# V4.net
KiCad netlist of a schematic drawn in Altium Designer
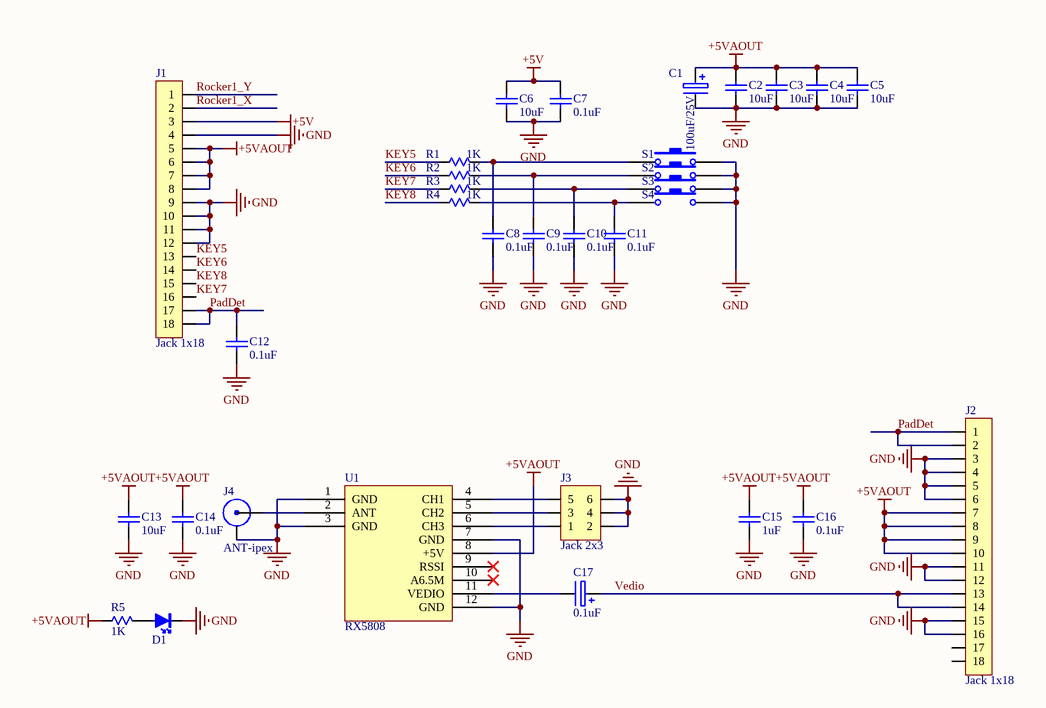
[diagram p0: 海关全向控制器图传转接板V4.SchDoc]

(export (version "E")
  (design (tool "Eeschema 10.0.6"))
  (components
    (comp (ref "C1") (value "100uF/25V") (footprint "C7343") (libsource (lib "RLCYDF") (part "Cap Poll")))
    (comp (ref "C2") (value "10uF") (footprint "C0805") (libsource (lib "SMD") (part "Cap Semi")))
    (comp (ref "C3") (value "10uF") (footprint "C0805") (libsource (lib "SMD") (part "Cap Semi")))
    (comp (ref "C4") (value "10uF") (footprint "C0805") (libsource (lib "SMD") (part "Cap Semi")))
    (comp (ref "C5") (value "10uF") (footprint "C0805") (libsource (lib "SMD") (part "Cap Semi")))
    (comp (ref "C6") (value "10uF") (footprint "C0805") (libsource (lib "SMD") (part "Cap Semi")))
    (comp (ref "C7") (value "0.1uF") (footprint "C0805") (libsource (lib "SMD") (part "Cap Semi")))
    (comp (ref "C8") (value "0.1uF") (footprint "C0805") (libsource (lib "SMD") (part "Cap Semi")))
    (comp (ref "C9") (value "0.1uF") (footprint "C0805") (libsource (lib "SMD") (part "Cap Semi")))
    (comp (ref "C10") (value "0.1uF") (footprint "C0805") (libsource (lib "SMD") (part "Cap Semi")))
    (comp (ref "C11") (value "0.1uF") (footprint "C0805") (libsource (lib "SMD") (part "Cap Semi")))
    (comp (ref "C12") (value "0.1uF") (footprint "C0805") (libsource (lib "SMD") (part "Cap Semi")))
    (comp (ref "C13") (value "10uF") (footprint "C0805") (libsource (lib "SMD") (part "Cap Semi")))
    (comp (ref "C14") (value "0.1uF") (footprint "C0805") (libsource (lib "SMD") (part "Cap Semi")))
    (comp (ref "C15") (value "1uF") (footprint "C0805") (libsource (lib "SMD") (part "Cap Semi")))
    (comp (ref "C16") (value "0.1uF") (footprint "C0805") (libsource (lib "SMD") (part "Cap Semi")))
    (comp (ref "C17") (value "0.1uF") (footprint "C10*10.8") (libsource (lib "RLCYDF") (part "Cap Poll")))
    (comp (ref "D1")
      (value "LED")
      (footprint "LED0805")
      (libsource (lib "Passive Components Class") (part "LED"))
    )
    (comp (ref "J1")
      (value "Jack 1x18")
      (footprint "0.5S-6X-18PB")
      (description "插座")
      (libsource (lib "") (part "Jack 1x18_1"))
    )
    (comp (ref "J2")
      (value "Jack 1x18")
      (footprint "0.5S-6X-18PB")
      (description "插座")
      (libsource (lib "Connector") (part "Jack 1x18"))
    )
    (comp (ref "J3")
      (value "Jack 2x3")
      (footprint "A6S-3101-PH")
      (description "双排座")
      (libsource (lib "Connector") (part "Jack 2x3"))
    )
    (comp (ref "J4") (value "ANT-ipex") (footprint "IPEX") (libsource (lib "RLCYDF") (part "ANT-ipex")))
    (comp (ref "R1")
      (value "1K")
      (footprint "R0805")
      (description "Resistor")
      (fields (field (name "PUBLISHER") "Altium Limited"))
      (libsource (lib "UP-Robot") (part "Res"))
    )
    (comp (ref "R2")
      (value "1K")
      (footprint "R0805")
      (description "Resistor")
      (fields (field (name "PUBLISHER") "Altium Limited"))
      (libsource (lib "UP-Robot") (part "Res"))
    )
    (comp (ref "R3")
      (value "1K")
      (footprint "R0805")
      (description "Resistor")
      (fields (field (name "PUBLISHER") "Altium Limited"))
      (libsource (lib "UP-Robot") (part "Res"))
    )
    (comp (ref "R4")
      (value "1K")
      (footprint "R0805")
      (description "Resistor")
      (fields (field (name "PUBLISHER") "Altium Limited"))
      (libsource (lib "UP-Robot") (part "Res"))
    )
    (comp (ref "R5")
      (value "1K")
      (footprint "R0805")
      (description "Resistor")
      (fields (field (name "PUBLISHER") "Altium Limited"))
      (libsource (lib "UP-Robot") (part "Res"))
    )
    (comp (ref "S1")
      (value "SW-PB")
      (footprint "SW3X6X5")
      (description "Switch")
      (fields (field (name "PUBLISHER") "Altium Limited"))
      (libsource (lib "Miscellaneous Devices") (part "SW-PB"))
    )
    (comp (ref "S2")
      (value "SW-PB")
      (footprint "SW3X6X5")
      (description "Switch")
      (fields (field (name "PUBLISHER") "Altium Limited"))
      (libsource (lib "Miscellaneous Devices") (part "SW-PB"))
    )
    (comp (ref "S3")
      (value "SW-PB")
      (footprint "SW3X6X5")
      (description "Switch")
      (fields (field (name "PUBLISHER") "Altium Limited"))
      (libsource (lib "Miscellaneous Devices") (part "SW-PB"))
    )
    (comp (ref "S4")
      (value "SW-PB")
      (footprint "SW3X6X5")
      (description "Switch")
      (fields (field (name "PUBLISHER") "Altium Limited"))
      (libsource (lib "Miscellaneous Devices") (part "SW-PB"))
    )
    (comp (ref "U1") (value "RX5808") (footprint "RX5808") (libsource (lib "Module") (part "RX5808")))
  )
  (nets
    (net (code "1") (name "+5V") (class "Default")
      (node (ref "C6") (pin "2") (pinfunction "2_2") (pintype "passive"))
      (node (ref "C7") (pin "2") (pinfunction "2_2") (pintype "passive"))
      (node (ref "J1") (pin "3") (pinfunction "3_3") (pintype "passive"))
    )
    (net (code "2") (name "+5VAOUT") (class "Default")
      (node (ref "C1") (pin "1") (pinfunction "1_1") (pintype "passive"))
      (node (ref "C13") (pin "2") (pinfunction "2_2") (pintype "passive"))
      (node (ref "C14") (pin "2") (pinfunction "2_2") (pintype "passive"))
      (node (ref "C15") (pin "2") (pinfunction "2_2") (pintype "passive"))
      (node (ref "C16") (pin "2") (pinfunction "2_2") (pintype "passive"))
      (node (ref "C2") (pin "2") (pinfunction "2_2") (pintype "passive"))
      (node (ref "C3") (pin "2") (pinfunction "2_2") (pintype "passive"))
      (node (ref "C4") (pin "2") (pinfunction "2_2") (pintype "passive"))
      (node (ref "C5") (pin "2") (pinfunction "2_2") (pintype "passive"))
      (node (ref "J1") (pin "5") (pinfunction "5_5") (pintype "passive"))
      (node (ref "J1") (pin "6") (pinfunction "6_6") (pintype "passive"))
      (node (ref "J1") (pin "7") (pinfunction "7_7") (pintype "passive"))
      (node (ref "J1") (pin "8") (pinfunction "8_8") (pintype "passive"))
      (node (ref "J2") (pin "10") (pinfunction "10_10") (pintype "passive"))
      (node (ref "J2") (pin "7") (pinfunction "7_7") (pintype "passive"))
      (node (ref "J2") (pin "8") (pinfunction "8_8") (pintype "passive"))
      (node (ref "J2") (pin "9") (pinfunction "9_9") (pintype "passive"))
      (node (ref "R5") (pin "1") (pinfunction "1_1") (pintype "passive"))
      (node (ref "U1") (pin "8") (pinfunction "+5V_8") (pintype "passive"))
    )
    (net (code "3") (name "/KEY5") (class "Default")
      (node (ref "J1") (pin "13") (pinfunction "13_13") (pintype "passive"))
      (node (ref "R1") (pin "1") (pinfunction "1_1") (pintype "passive"))
    )
    (net (code "4") (name "/KEY6") (class "Default")
      (node (ref "J1") (pin "14") (pinfunction "14_14") (pintype "passive"))
      (node (ref "R2") (pin "1") (pinfunction "1_1") (pintype "passive"))
    )
    (net (code "5") (name "/KEY7") (class "Default")
      (node (ref "J1") (pin "16") (pinfunction "16_16") (pintype "passive"))
      (node (ref "R3") (pin "1") (pinfunction "1_1") (pintype "passive"))
    )
    (net (code "6") (name "/KEY8") (class "Default")
      (node (ref "J1") (pin "15") (pinfunction "15_15") (pintype "passive"))
      (node (ref "R4") (pin "1") (pinfunction "1_1") (pintype "passive"))
    )
    (net (code "7") (name "/PadDet") (class "Default")
      (node (ref "C12") (pin "2") (pinfunction "2_2") (pintype "passive"))
      (node (ref "J1") (pin "17") (pinfunction "17_17") (pintype "passive"))
      (node (ref "J1") (pin "18") (pinfunction "18_18") (pintype "passive"))
      (node (ref "J2") (pin "1") (pinfunction "1_1") (pintype "passive"))
      (node (ref "J2") (pin "2") (pinfunction "2_2") (pintype "passive"))
    )
    (net (code "8") (name "/Rocker1_X") (class "Default")
      (node (ref "J1") (pin "2") (pinfunction "2_2") (pintype "passive"))
    )
    (net (code "9") (name "/Rocker1_Y") (class "Default")
      (node (ref "J1") (pin "1") (pinfunction "1_1") (pintype "passive"))
    )
    (net (code "10") (name "/Vedio") (class "Default")
      (node (ref "C17") (pin "1") (pinfunction "1_1") (pintype "passive"))
      (node (ref "J2") (pin "13") (pinfunction "13_13") (pintype "passive"))
      (node (ref "J2") (pin "14") (pinfunction "14_14") (pintype "passive"))
    )
    (net (code "11") (name "GND") (class "Default")
      (node (ref "C1") (pin "2") (pinfunction "2_2") (pintype "passive"))
      (node (ref "C10") (pin "1") (pinfunction "1_1") (pintype "passive"))
      (node (ref "C11") (pin "1") (pinfunction "1_1") (pintype "passive"))
      (node (ref "C12") (pin "1") (pinfunction "1_1") (pintype "passive"))
      (node (ref "C13") (pin "1") (pinfunction "1_1") (pintype "passive"))
      (node (ref "C14") (pin "1") (pinfunction "1_1") (pintype "passive"))
      (node (ref "C15") (pin "1") (pinfunction "1_1") (pintype "passive"))
      (node (ref "C16") (pin "1") (pinfunction "1_1") (pintype "passive"))
      (node (ref "C2") (pin "1") (pinfunction "1_1") (pintype "passive"))
      (node (ref "C3") (pin "1") (pinfunction "1_1") (pintype "passive"))
      (node (ref "C4") (pin "1") (pinfunction "1_1") (pintype "passive"))
      (node (ref "C5") (pin "1") (pinfunction "1_1") (pintype "passive"))
      (node (ref "C6") (pin "1") (pinfunction "1_1") (pintype "passive"))
      (node (ref "C7") (pin "1") (pinfunction "1_1") (pintype "passive"))
      (node (ref "C8") (pin "1") (pinfunction "1_1") (pintype "passive"))
      (node (ref "C9") (pin "1") (pinfunction "1_1") (pintype "passive"))
      (node (ref "D1") (pin "2") (pinfunction "K_2") (pintype "passive"))
      (node (ref "J1") (pin "10") (pinfunction "10_10") (pintype "passive"))
      (node (ref "J1") (pin "11") (pinfunction "11_11") (pintype "passive"))
      (node (ref "J1") (pin "12") (pinfunction "12_12") (pintype "passive"))
      (node (ref "J1") (pin "4") (pinfunction "4_4") (pintype "passive"))
      (node (ref "J1") (pin "9") (pinfunction "9_9") (pintype "passive"))
      (node (ref "J2") (pin "11") (pinfunction "11_11") (pintype "passive"))
      (node (ref "J2") (pin "12") (pinfunction "12_12") (pintype "passive"))
      (node (ref "J2") (pin "15") (pinfunction "15_15") (pintype "passive"))
      (node (ref "J2") (pin "16") (pinfunction "16_16") (pintype "passive"))
      (node (ref "J2") (pin "3") (pinfunction "3_3") (pintype "passive"))
      (node (ref "J2") (pin "4") (pinfunction "4_4") (pintype "passive"))
      (node (ref "J2") (pin "5") (pinfunction "5_5") (pintype "passive"))
      (node (ref "J2") (pin "6") (pinfunction "6_6") (pintype "passive"))
      (node (ref "J3") (pin "2") (pinfunction "2_2") (pintype "passive"))
      (node (ref "J3") (pin "4") (pinfunction "4_4") (pintype "passive"))
      (node (ref "J3") (pin "6") (pinfunction "6_6") (pintype "passive"))
      (node (ref "J4") (pin "2") (pinfunction "GND_2") (pintype "passive"))
      (node (ref "S1") (pin "2") (pinfunction "2_2") (pintype "passive"))
      (node (ref "S2") (pin "2") (pinfunction "2_2") (pintype "passive"))
      (node (ref "S3") (pin "2") (pinfunction "2_2") (pintype "passive"))
      (node (ref "S4") (pin "2") (pinfunction "2_2") (pintype "passive"))
      (node (ref "U1") (pin "1") (pinfunction "GND_1") (pintype "passive"))
      (node (ref "U1") (pin "12") (pinfunction "GND_12") (pintype "passive"))
      (node (ref "U1") (pin "3") (pinfunction "GND_3") (pintype "passive"))
      (node (ref "U1") (pin "7") (pinfunction "GND_7") (pintype "passive"))
    )
    (net (code "12") (name "Net-(C8-Pad2)") (class "Default")
      (node (ref "C8") (pin "2") (pinfunction "2_2") (pintype "passive"))
      (node (ref "R1") (pin "2") (pinfunction "2_2") (pintype "passive"))
      (node (ref "S1") (pin "1") (pinfunction "1_1") (pintype "passive"))
    )
    (net (code "13") (name "Net-(C9-Pad2)") (class "Default")
      (node (ref "C9") (pin "2") (pinfunction "2_2") (pintype "passive"))
      (node (ref "R2") (pin "2") (pinfunction "2_2") (pintype "passive"))
      (node (ref "S2") (pin "1") (pinfunction "1_1") (pintype "passive"))
    )
    (net (code "14") (name "Net-(C10-Pad2)") (class "Default")
      (node (ref "C10") (pin "2") (pinfunction "2_2") (pintype "passive"))
      (node (ref "R3") (pin "2") (pinfunction "2_2") (pintype "passive"))
      (node (ref "S3") (pin "1") (pinfunction "1_1") (pintype "passive"))
    )
    (net (code "15") (name "Net-(C11-Pad2)") (class "Default")
      (node (ref "C11") (pin "2") (pinfunction "2_2") (pintype "passive"))
      (node (ref "R4") (pin "2") (pinfunction "2_2") (pintype "passive"))
      (node (ref "S4") (pin "1") (pinfunction "1_1") (pintype "passive"))
    )
    (net (code "16") (name "Net-(D1-A)") (class "Default")
      (node (ref "D1") (pin "1") (pinfunction "A_1") (pintype "passive"))
      (node (ref "R5") (pin "2") (pinfunction "2_2") (pintype "passive"))
    )
    (net (code "17") (name "Net-(J4-ANT)") (class "Default")
      (node (ref "J4") (pin "1") (pinfunction "ANT_1") (pintype "passive"))
      (node (ref "U1") (pin "2") (pinfunction "ANT_2") (pintype "passive"))
    )
    (net (code "18") (name "Net-(U1-CH1)") (class "Default")
      (node (ref "J3") (pin "5") (pinfunction "5_5") (pintype "passive"))
      (node (ref "U1") (pin "4") (pinfunction "CH1_4") (pintype "passive"))
    )
    (net (code "19") (name "Net-(U1-CH2)") (class "Default")
      (node (ref "J3") (pin "3") (pinfunction "3_3") (pintype "passive"))
      (node (ref "U1") (pin "5") (pinfunction "CH2_5") (pintype "passive"))
    )
    (net (code "20") (name "Net-(U1-CH3)") (class "Default")
      (node (ref "J3") (pin "1") (pinfunction "1_1") (pintype "passive"))
      (node (ref "U1") (pin "6") (pinfunction "CH3_6") (pintype "passive"))
    )
    (net (code "21") (name "Net-(U1-VEDIO)") (class "Default")
      (node (ref "C17") (pin "2") (pinfunction "2_2") (pintype "passive"))
      (node (ref "U1") (pin "11") (pinfunction "VEDIO_11") (pintype "passive"))
    )
    (net (code "22") (name "unconnected-(J2-Pad17)") (class "Default")
      (node (ref "J2") (pin "17") (pinfunction "17_17") (pintype "passive"))
    )
    (net (code "23") (name "unconnected-(J2-Pad18)") (class "Default")
      (node (ref "J2") (pin "18") (pinfunction "18_18") (pintype "passive"))
    )
    (net (code "24") (name "unconnected-(U1-A6.5M-Pad10)") (class "Default")
      (node (ref "U1") (pin "10") (pinfunction "A6.5M_10") (pintype "passive+no_connect"))
    )
    (net (code "25") (name "unconnected-(U1-RSSI-Pad9)") (class "Default")
      (node (ref "U1") (pin "9") (pinfunction "RSSI_9") (pintype "passive+no_connect"))
    )
  )
)
